# PowerIn.net
KiCad netlist of a schematic drawn in Altium Designer
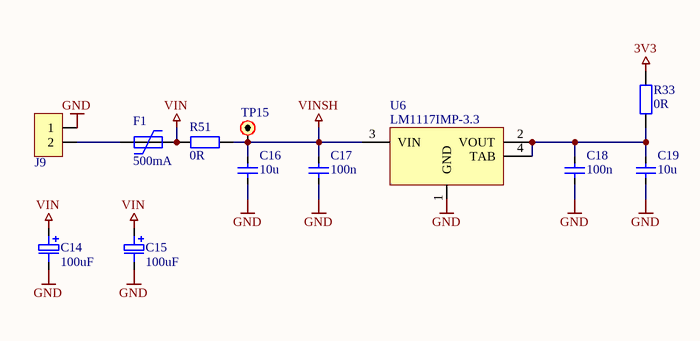
[diagram p0: PowerIn.SchDoc]

(export (version "E")
  (design (tool "Eeschema 10.0.6"))
  (components
    (comp (ref "C14")
      (value "100uF")
      (footprint "C_EL_B_4MM_RF_M")
      (description "Polarized Capacitor")
      (fields (field (name "TOLERANCE") "?") (field (name "MANUFACTURER") "Generic Brand"))
      (libsource (lib "AG.Generic") (part "C-P"))
    )
    (comp (ref "C15")
      (value "100uF")
      (footprint "C_EL_B_4MM_RF_M")
      (description "Polarized Capacitor")
      (fields (field (name "TOLERANCE") "?") (field (name "MANUFACTURER") "Generic Brand"))
      (libsource (lib "AG.Generic") (part "C-P"))
    )
    (comp (ref "C16")
      (value "10u")
      (footprint "0805C_RF_M")
      (description "Capacitor")
      (fields (field (name "TOLERANCE") "?") (field (name "MANUFACTURER") "Generic Brand"))
      (libsource (lib "AG.Generic") (part "C"))
    )
    (comp (ref "C17")
      (value "100n")
      (footprint "0805C_RF_M")
      (description "Capacitor")
      (fields (field (name "TOLERANCE") "?") (field (name "MANUFACTURER") "Generic Brand"))
      (libsource (lib "AG.Generic") (part "C"))
    )
    (comp (ref "C18")
      (value "100n")
      (footprint "0805C_RF_M")
      (description "Capacitor")
      (fields (field (name "TOLERANCE") "?") (field (name "MANUFACTURER") "Generic Brand"))
      (libsource (lib "AG.Generic") (part "C"))
    )
    (comp (ref "C19")
      (value "10u")
      (footprint "0805C_RF_M")
      (description "Capacitor")
      (fields (field (name "TOLERANCE") "?") (field (name "MANUFACTURER") "Generic Brand"))
      (libsource (lib "AG.Generic") (part "C"))
    )
    (comp (ref "F1")
      (value "500mA")
      (footprint "BOURNS_MF-MSMF110/16-2_RF_H")
      (description "Resettable Fuse")
      (fields (field (name "MANUFACTURER") "Generic Brand"))
      (libsource (lib "AG.Generic") (part "PPTC"))
    )
    (comp (ref "J9")
      (value "PINHDR-2P1")
      (footprint "HEADER-2.54-2P1")
      (description "Pin Header Single Row 2 Positions")
      (libsource (lib "AG.Connectors") (part "PINHDR-2P1"))
    )
    (comp (ref "R33")
      (value "0R")
      (footprint "1206R_RF_M")
      (description "Resistor")
      (fields (field (name "TOLERANCE") "?") (field (name "MANUFACTURER") "Generic Brand"))
      (libsource (lib "AG.Generic") (part "R"))
    )
    (comp (ref "R51")
      (value "0R")
      (footprint "1206R_RF_M")
      (description "Resistor")
      (fields (field (name "TOLERANCE") "?") (field (name "MANUFACTURER") "Generic Brand"))
      (libsource (lib "AG.Generic") (part "R"))
    )
    (comp (ref "TP15")
      (value "5V")
      (footprint "PAD_R_1.5MM")
      (description "Test Point / Pad")
      (libsource (lib "AG.Misc") (part "Test Point"))
    )
    (comp (ref "U6")
      (value "LM1117IMP-3.3")
      (footprint "SOT-223")
      (description "Voltage Regulator Linear 1% 800mA SOT-223")
      (fields (field (name "MANUFACTURER") "Texas Instruments"))
      (libsource (lib "AG.IC") (part "LM1117"))
    )
  )
  (nets
    (net (code "1") (name "3V3") (class "Default") (node (ref "R33") (pin "2") (pintype "passive")))
    (net (code "2") (name "GND") (class "Default")
      (node (ref "C14") (pin "N") (pinfunction "N_N") (pintype "power_in"))
      (node (ref "C15") (pin "N") (pinfunction "N_N") (pintype "power_in"))
      (node (ref "C16") (pin "1") (pinfunction "1_1") (pintype "passive"))
      (node (ref "C17") (pin "1") (pinfunction "1_1") (pintype "passive"))
      (node (ref "C18") (pin "1") (pinfunction "1_1") (pintype "passive"))
      (node (ref "C19") (pin "1") (pinfunction "1_1") (pintype "passive"))
      (node (ref "J9") (pin "1") (pinfunction "1_1") (pintype "passive"))
      (node (ref "U6") (pin "1") (pinfunction "GND_1") (pintype "passive"))
    )
    (net (code "3") (name "Net-(F1-Pad2)") (class "Default")
      (node (ref "F1") (pin "2") (pinfunction "2_2") (pintype "passive"))
      (node (ref "J9") (pin "2") (pinfunction "2_2") (pintype "passive"))
    )
    (net (code "4") (name "Net-(U6-TAB)") (class "Default")
      (node (ref "C18") (pin "2") (pinfunction "2_2") (pintype "passive"))
      (node (ref "C19") (pin "2") (pinfunction "2_2") (pintype "passive"))
      (node (ref "R33") (pin "1") (pintype "passive"))
      (node (ref "U6") (pin "2") (pinfunction "VOUT_2") (pintype "passive"))
      (node (ref "U6") (pin "4") (pinfunction "TAB_4") (pintype "passive"))
    )
    (net (code "5") (name "VIN") (class "Default")
      (node (ref "C14") (pin "P") (pinfunction "P_P") (pintype "power_in"))
      (node (ref "C15") (pin "P") (pinfunction "P_P") (pintype "power_in"))
      (node (ref "F1") (pin "1") (pinfunction "1_1") (pintype "passive"))
      (node (ref "R51") (pin "1") (pintype "passive"))
    )
    (net (code "6") (name "VINSH") (class "Default")
      (node (ref "C16") (pin "2") (pinfunction "2_2") (pintype "passive"))
      (node (ref "C17") (pin "2") (pinfunction "2_2") (pintype "passive"))
      (node (ref "R51") (pin "2") (pintype "passive"))
      (node (ref "TP15") (pin "1") (pinfunction "1_1") (pintype "passive"))
      (node (ref "U6") (pin "3") (pinfunction "VIN_3") (pintype "passive"))
    )
  )
)
